# lps25h_board.net
KiCad netlist of a schematic drawn in EAGLE
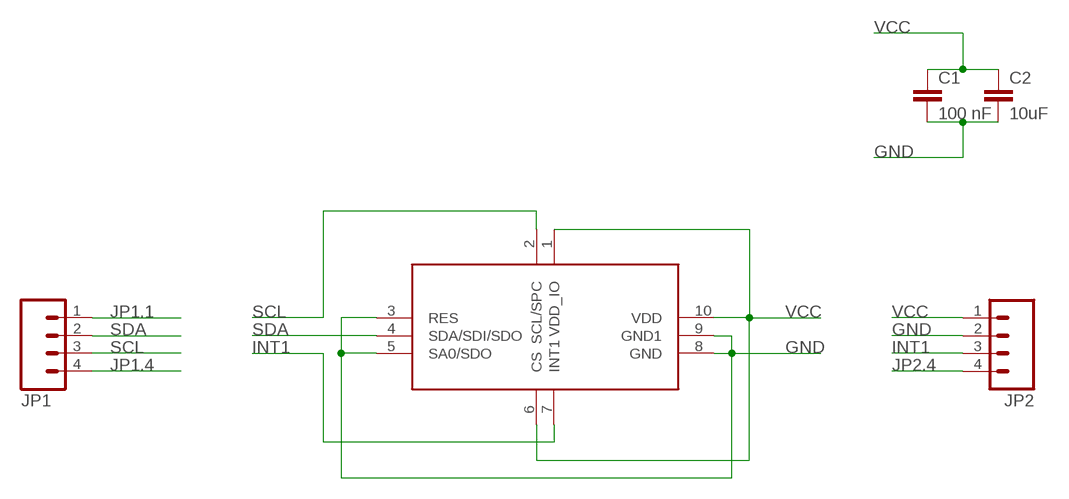
[diagram p0: schematic, sheet 1]

(export (version "E")
  (design (tool "Eeschema 10.0.6"))
  (components
    (comp (ref "C1")
      (value "100 nF")
      (footprint "eagle-import:0805-CAP")
      (libsource (lib "eagle-import") (part "CAP0805-CAP"))
    )
    (comp (ref "C2")
      (value "10uF")
      (footprint "eagle-import:0805-CAP")
      (libsource (lib "eagle-import") (part "CAP0805-CAP"))
    )
    (comp (ref "JP1")
      (value "M04PTH")
      (footprint "eagle-import:1X04")
      (libsource (lib "eagle-import") (part "M04PTH"))
    )
    (comp (ref "JP2")
      (value "M04PTH")
      (footprint "eagle-import:1X04")
      (libsource (lib "eagle-import") (part "M04PTH"))
    )
    (comp (ref "U$1")
      (value "LPS25HLPS25H")
      (footprint "eagle-import:LPS25H")
      (libsource (lib "eagle-import") (part "LPS25HLPS25H"))
    )
  )
  (nets
    (net (code "1") (name "/GND") (class "Default")
      (node (ref "C1") (pin "2") (pinfunction "2_2") (pintype "passive"))
      (node (ref "C2") (pin "2") (pinfunction "2_2") (pintype "passive"))
      (node (ref "JP2") (pin "2") (pinfunction "2_2") (pintype "passive"))
      (node (ref "U$1") (pin "3") (pinfunction "RES_3") (pintype "bidirectional"))
      (node (ref "U$1") (pin "5") (pinfunction "SA0/SDO_5") (pintype "bidirectional"))
      (node (ref "U$1") (pin "8") (pinfunction "GND_8") (pintype "bidirectional"))
      (node (ref "U$1") (pin "9") (pinfunction "GND1_9") (pintype "bidirectional"))
    )
    (net (code "2") (name "/INT1") (class "Default")
      (node (ref "JP2") (pin "3") (pinfunction "3_3") (pintype "passive"))
      (node (ref "U$1") (pin "7") (pinfunction "INT1_7") (pintype "bidirectional"))
    )
    (net (code "3") (name "/JP1.1") (class "Default")
      (node (ref "JP1") (pin "1") (pinfunction "1_1") (pintype "passive"))
    )
    (net (code "4") (name "/JP1.4") (class "Default")
      (node (ref "JP1") (pin "4") (pinfunction "4_4") (pintype "passive"))
    )
    (net (code "5") (name "/JP2.4") (class "Default")
      (node (ref "JP2") (pin "4") (pinfunction "4_4") (pintype "passive"))
    )
    (net (code "6") (name "/SCL") (class "Default")
      (node (ref "JP1") (pin "3") (pinfunction "3_3") (pintype "passive"))
      (node (ref "U$1") (pin "2") (pinfunction "SCL/SPC_2") (pintype "bidirectional"))
    )
    (net (code "7") (name "/SDA") (class "Default")
      (node (ref "JP1") (pin "2") (pinfunction "2_2") (pintype "passive"))
      (node (ref "U$1") (pin "4") (pinfunction "SDA/SDI/SDO_4") (pintype "bidirectional"))
    )
    (net (code "8") (name "/VCC") (class "Default")
      (node (ref "C1") (pin "1") (pinfunction "1_1") (pintype "passive"))
      (node (ref "C2") (pin "1") (pinfunction "1_1") (pintype "passive"))
      (node (ref "JP2") (pin "1") (pinfunction "1_1") (pintype "passive"))
      (node (ref "U$1") (pin "1") (pinfunction "VDD_IO_1") (pintype "bidirectional"))
      (node (ref "U$1") (pin "10") (pinfunction "VDD_10") (pintype "bidirectional"))
      (node (ref "U$1") (pin "6") (pinfunction "CS_6") (pintype "bidirectional"))
    )
  )
)
